# schematic.net
KiCad netlist of a schematic drawn in EasyEDA
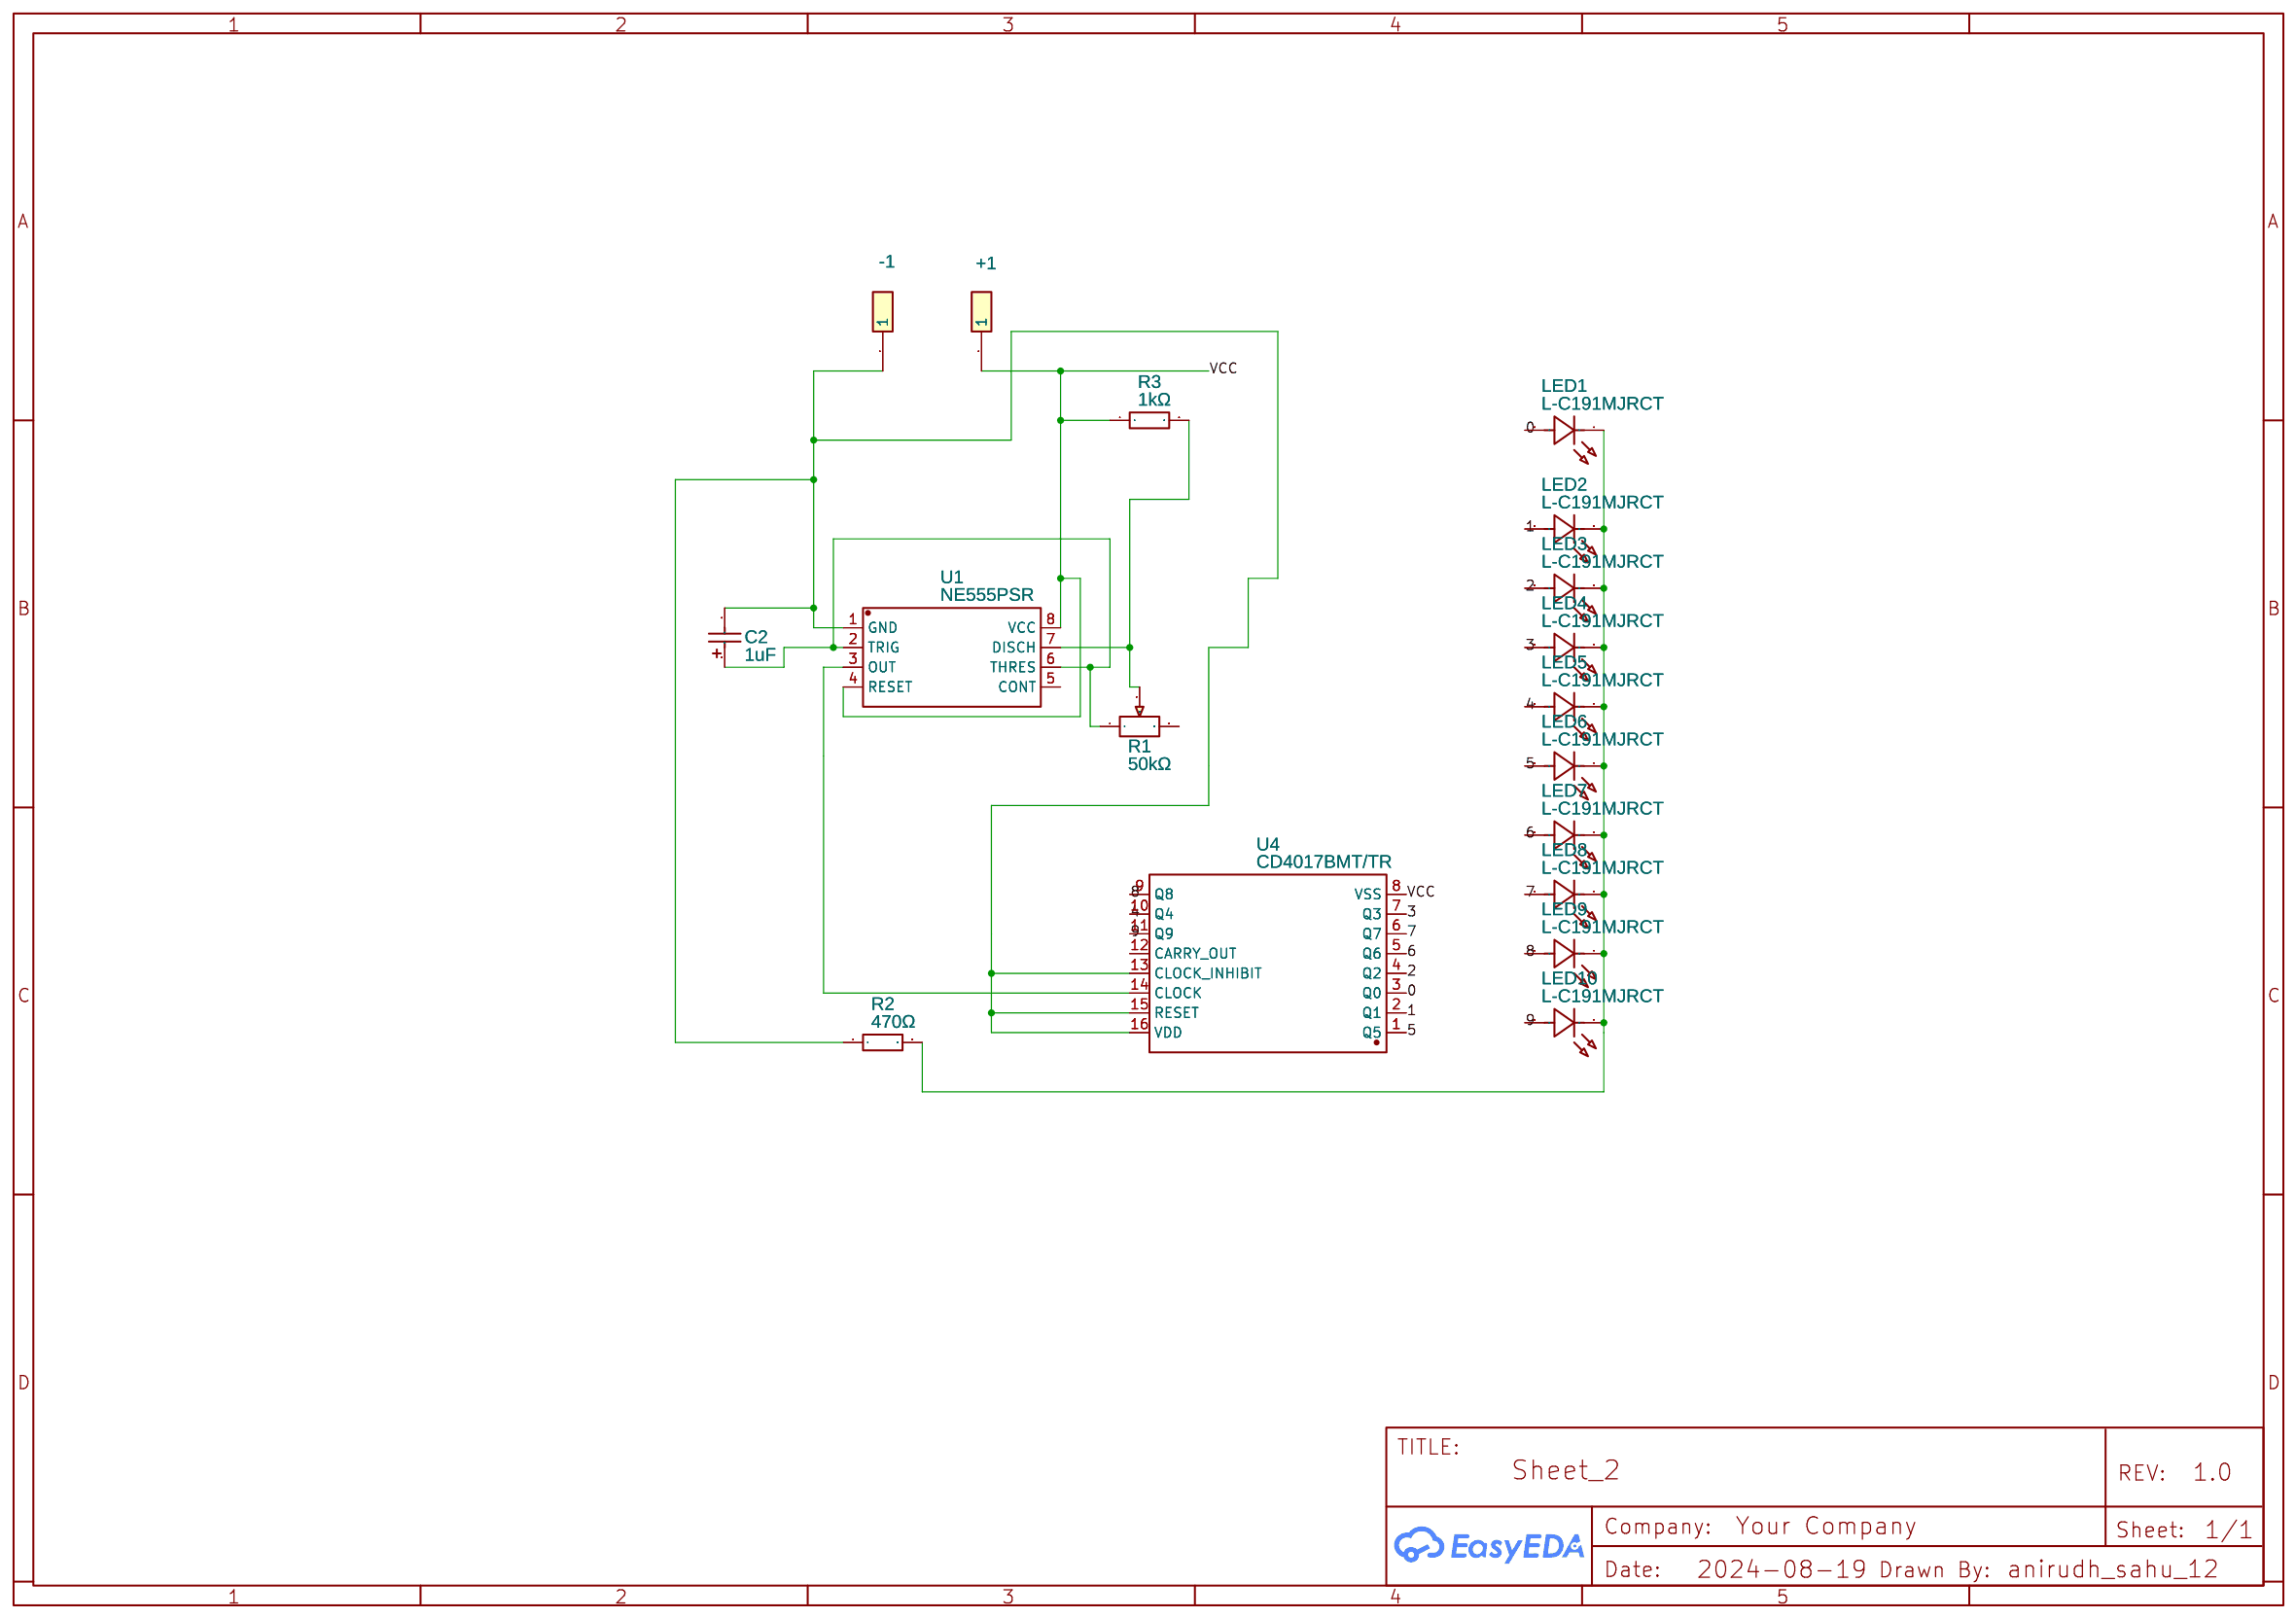
[diagram p0: schematic sheet]

(export (version "E")
  (design (tool "Eeschema 10.0.6"))
  (components
    (comp (ref "+1")
      (value "Header-Male-2.54_1x1")
      (fields (field (name "Manufacturer") "LCSC"))
      (libsource (lib "") (part "Unknown_490_-640"))
    )
    (comp (ref "-1")
      (value "Header-Male-2.54_1x1")
      (fields (field (name "Manufacturer") "LCSC"))
      (libsource (lib "") (part "Unknown_440_-640"))
    )
    (comp (ref "C2")
      (value "1uF")
      (fields (field (name "Manufacturer Part") "TAJB105K050RNJ") (field (name "Manufacturer") "Kyocera AVX"))
      (libsource (lib "") (part "TAJB105K050RNJ"))
    )
    (comp (ref "LED1")
      (value "L-C191MJRCT")
      (fields (field (name "Manufacturer") "PARALIGHT(光鼎)"))
      (libsource (lib "") (part "L-C191MJRCT"))
    )
    (comp (ref "LED2")
      (value "L-C191MJRCT")
      (fields (field (name "Manufacturer") "PARALIGHT(光鼎)"))
      (libsource (lib "") (part "L-C191MJRCT"))
    )
    (comp (ref "LED3")
      (value "L-C191MJRCT")
      (fields (field (name "Manufacturer") "PARALIGHT(光鼎)"))
      (libsource (lib "") (part "L-C191MJRCT"))
    )
    (comp (ref "LED4")
      (value "L-C191MJRCT")
      (fields (field (name "Manufacturer") "PARALIGHT(光鼎)"))
      (libsource (lib "") (part "L-C191MJRCT"))
    )
    (comp (ref "LED5")
      (value "L-C191MJRCT")
      (fields (field (name "Manufacturer") "PARALIGHT(光鼎)"))
      (libsource (lib "") (part "L-C191MJRCT"))
    )
    (comp (ref "LED6")
      (value "L-C191MJRCT")
      (fields (field (name "Manufacturer") "PARALIGHT(光鼎)"))
      (libsource (lib "") (part "L-C191MJRCT"))
    )
    (comp (ref "LED7")
      (value "L-C191MJRCT")
      (fields (field (name "Manufacturer") "PARALIGHT(光鼎)"))
      (libsource (lib "") (part "L-C191MJRCT"))
    )
    (comp (ref "LED8")
      (value "L-C191MJRCT")
      (fields (field (name "Manufacturer") "PARALIGHT(光鼎)"))
      (libsource (lib "") (part "L-C191MJRCT"))
    )
    (comp (ref "LED9")
      (value "L-C191MJRCT")
      (fields (field (name "Manufacturer") "PARALIGHT(光鼎)"))
      (libsource (lib "") (part "L-C191MJRCT"))
    )
    (comp (ref "LED10")
      (value "L-C191MJRCT")
      (fields (field (name "Manufacturer") "PARALIGHT(光鼎)"))
      (libsource (lib "") (part "L-C191MJRCT"))
    )
    (comp (ref "R1")
      (value "50kΩ")
      (fields (field (name "Manufacturer Part") "3362P-1-503") (field (name "Manufacturer") "BOCHEN(博晨)"))
      (libsource (lib "") (part "3362P-1-503"))
    )
    (comp (ref "R2")
      (value "470Ω")
      (fields
        (field (name "Manufacturer Part") "MFR0W4F4700A50")
        (field (name "Manufacturer") "UNI-ROYAL(厚声)")
      )
      (libsource (lib "") (part "MFR0W4F4700A50"))
    )
    (comp (ref "R3")
      (value "1kΩ")
      (fields
        (field (name "Manufacturer Part") "MFR0W4F1001A50")
        (field (name "Manufacturer") "UNI-ROYAL(厚声)")
      )
      (libsource (lib "") (part "MFR0W4F1001A50"))
    )
    (comp (ref "U1")
      (value "NE555PSR")
      (fields (field (name "Manufacturer") "TI(德州仪器)"))
      (libsource (lib "") (part "NE555PSR"))
    )
    (comp (ref "U4")
      (value "CD4017BMT/TR")
      (fields (field (name "Manufacturer") "HGSEMI(华冠)"))
      (libsource (lib "") (part "CD4017BMT/TR"))
    )
  )
  (nets
    (net (code "1") (name "/0") (class "Default")
      (node (ref "LED1") (pin "2") (pinfunction "A_2") (pintype "unspecified"))
      (node (ref "U4") (pin "3") (pinfunction "Q0_3") (pintype "unspecified"))
    )
    (net (code "2") (name "/1") (class "Default")
      (node (ref "LED2") (pin "2") (pinfunction "A_2") (pintype "unspecified"))
      (node (ref "U4") (pin "2") (pinfunction "Q1_2") (pintype "unspecified"))
    )
    (net (code "3") (name "/2") (class "Default")
      (node (ref "LED3") (pin "2") (pinfunction "A_2") (pintype "unspecified"))
      (node (ref "U4") (pin "4") (pinfunction "Q2_4") (pintype "unspecified"))
    )
    (net (code "4") (name "/3") (class "Default")
      (node (ref "LED4") (pin "2") (pinfunction "A_2") (pintype "unspecified"))
      (node (ref "U4") (pin "7") (pinfunction "Q3_7") (pintype "unspecified"))
    )
    (net (code "5") (name "/4") (class "Default")
      (node (ref "LED5") (pin "2") (pinfunction "A_2") (pintype "unspecified"))
      (node (ref "U4") (pin "10") (pinfunction "Q4_10") (pintype "unspecified"))
    )
    (net (code "6") (name "/5") (class "Default")
      (node (ref "LED6") (pin "2") (pinfunction "A_2") (pintype "unspecified"))
      (node (ref "U4") (pin "1") (pinfunction "Q5_1") (pintype "unspecified"))
    )
    (net (code "7") (name "/6") (class "Default")
      (node (ref "LED7") (pin "2") (pinfunction "A_2") (pintype "unspecified"))
      (node (ref "U4") (pin "5") (pinfunction "Q6_5") (pintype "unspecified"))
    )
    (net (code "8") (name "/7") (class "Default")
      (node (ref "LED8") (pin "2") (pinfunction "A_2") (pintype "unspecified"))
      (node (ref "U4") (pin "6") (pinfunction "Q7_6") (pintype "unspecified"))
    )
    (net (code "9") (name "/8") (class "Default")
      (node (ref "LED9") (pin "2") (pinfunction "A_2") (pintype "unspecified"))
      (node (ref "U4") (pin "9") (pinfunction "Q8_9") (pintype "unspecified"))
    )
    (net (code "10") (name "/9") (class "Default")
      (node (ref "LED10") (pin "2") (pinfunction "A_2") (pintype "unspecified"))
      (node (ref "U4") (pin "11") (pinfunction "Q9_11") (pintype "unspecified"))
    )
    (net (code "11") (name "/VCC") (class "Default")
      (node (ref "+1") (pin "1") (pinfunction "1_1") (pintype "input"))
      (node (ref "R3") (pin "1") (pinfunction "1_1") (pintype "input"))
      (node (ref "U1") (pin "4") (pinfunction "RESET_4") (pintype "unspecified"))
      (node (ref "U1") (pin "8") (pinfunction "VCC_8") (pintype "unspecified"))
      (node (ref "U4") (pin "8") (pinfunction "VSS_8") (pintype "unspecified"))
    )
    (net (code "12") (name "Net-(LED1-K)") (class "Default")
      (node (ref "LED1") (pin "1") (pinfunction "K_1") (pintype "unspecified"))
      (node (ref "LED10") (pin "1") (pinfunction "K_1") (pintype "unspecified"))
      (node (ref "LED2") (pin "1") (pinfunction "K_1") (pintype "unspecified"))
      (node (ref "LED3") (pin "1") (pinfunction "K_1") (pintype "unspecified"))
      (node (ref "LED4") (pin "1") (pinfunction "K_1") (pintype "unspecified"))
      (node (ref "LED5") (pin "1") (pinfunction "K_1") (pintype "unspecified"))
      (node (ref "LED6") (pin "1") (pinfunction "K_1") (pintype "unspecified"))
      (node (ref "LED7") (pin "1") (pinfunction "K_1") (pintype "unspecified"))
      (node (ref "LED8") (pin "1") (pinfunction "K_1") (pintype "unspecified"))
      (node (ref "LED9") (pin "1") (pinfunction "K_1") (pintype "unspecified"))
      (node (ref "R2") (pin "2") (pinfunction "2_2") (pintype "input"))
    )
    (net (code "13") (name "Net-(U1-DISCH)") (class "Default")
      (node (ref "R1") (pin "2") (pinfunction "2_2") (pintype "input"))
      (node (ref "R3") (pin "2") (pinfunction "2_2") (pintype "input"))
      (node (ref "U1") (pin "7") (pinfunction "DISCH_7") (pintype "unspecified"))
    )
    (net (code "14") (name "Net-(U1-GND)") (class "Default")
      (node (ref "-1") (pin "1") (pinfunction "1_1") (pintype "input"))
      (node (ref "C2") (pin "2") (pinfunction "2_2") (pintype "input"))
      (node (ref "R2") (pin "1") (pinfunction "1_1") (pintype "input"))
      (node (ref "U1") (pin "1") (pinfunction "GND_1") (pintype "unspecified"))
      (node (ref "U4") (pin "13") (pinfunction "CLOCK_INHIBIT_13") (pintype "unspecified"))
      (node (ref "U4") (pin "15") (pinfunction "RESET_15") (pintype "unspecified"))
      (node (ref "U4") (pin "16") (pinfunction "VDD_16") (pintype "unspecified"))
    )
    (net (code "15") (name "Net-(U1-OUT)") (class "Default")
      (node (ref "U1") (pin "3") (pinfunction "OUT_3") (pintype "unspecified"))
      (node (ref "U4") (pin "14") (pinfunction "CLOCK_14") (pintype "unspecified"))
    )
    (net (code "16") (name "Net-(U1-THRES)") (class "Default")
      (node (ref "C2") (pin "1") (pinfunction "1_1") (pintype "input"))
      (node (ref "R1") (pin "1") (pinfunction "1_1") (pintype "input"))
      (node (ref "U1") (pin "2") (pinfunction "TRIG_2") (pintype "unspecified"))
      (node (ref "U1") (pin "6") (pinfunction "THRES_6") (pintype "unspecified"))
    )
    (net (code "17") (name "unconnected-(R1-Pad3)") (class "Default")
      (node (ref "R1") (pin "3") (pinfunction "3_3") (pintype "input"))
    )
    (net (code "18") (name "unconnected-(U1-CONT-Pad5)") (class "Default")
      (node (ref "U1") (pin "5") (pinfunction "CONT_5") (pintype "unspecified"))
    )
    (net (code "19") (name "unconnected-(U4-CARRY_OUT-Pad12)") (class "Default")
      (node (ref "U4") (pin "12") (pinfunction "CARRY_OUT_12") (pintype "unspecified"))
    )
  )
)
